# switch.net
KiCad netlist of a schematic drawn in EAGLE
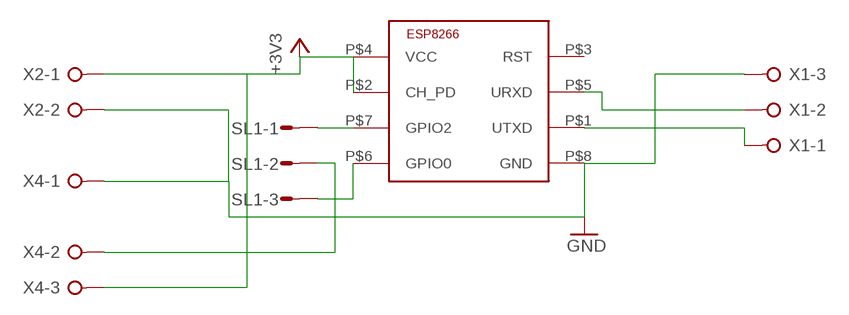
[diagram p0: schematic, sheet 1]

(export (version "E")
  (design (tool "Eeschema 10.0.6"))
  (components
    (comp (ref "SL1")
      (value "M03S")
      (footprint "eagle-import:03P")
      (libsource (lib "eagle-import") (part "M03S"))
    )
    (comp (ref "U$1")
      (value "ESP8266-01")
      (footprint "eagle-import:ESP-01")
      (libsource (lib "eagle-import") (part "ESP8266-01"))
    )
    (comp (ref "X1")
      (value "W237-3E")
      (footprint "eagle-import:W237-3E")
      (libsource (lib "eagle-import") (part "W237-3E"))
    )
    (comp (ref "X2")
      (value "W237-02P")
      (footprint "eagle-import:W237-132")
      (libsource (lib "eagle-import") (part "W237-02P"))
    )
    (comp (ref "X4")
      (value "W237-3E")
      (footprint "eagle-import:W237-3E")
      (libsource (lib "eagle-import") (part "W237-3E"))
    )
  )
  (nets
    (net (code "1") (name "+3V3") (class "Default")
      (node (ref "U$1") (pin "P$2") (pinfunction "CH_PD_P$2") (pintype "bidirectional"))
      (node (ref "U$1") (pin "P$4") (pinfunction "VCC_P$4") (pintype "bidirectional"))
      (node (ref "X2") (pin "1") (pinfunction "KL_1") (pintype "passive"))
      (node (ref "X4") (pin "3") (pinfunction "KL_3") (pintype "passive"))
    )
    (net (code "2") (name "GND") (class "Default")
      (node (ref "U$1") (pin "P$8") (pinfunction "GND_P$8") (pintype "bidirectional"))
      (node (ref "X1") (pin "3") (pinfunction "KL_3") (pintype "passive"))
      (node (ref "X2") (pin "2") (pinfunction "KL_2") (pintype "passive"))
      (node (ref "X4") (pin "1") (pinfunction "KL_1") (pintype "passive"))
    )
    (net (code "3") (name "Net-(SL1A-S)") (class "Default")
      (node (ref "SL1") (pin "1") (pinfunction "S_1") (pintype "passive"))
      (node (ref "U$1") (pin "P$7") (pinfunction "GPIO2_P$7") (pintype "bidirectional"))
    )
    (net (code "4") (name "Net-(SL1B-S)") (class "Default")
      (node (ref "SL1") (pin "2") (pinfunction "S_2") (pintype "passive"))
      (node (ref "X4") (pin "2") (pinfunction "KL_2") (pintype "passive"))
    )
    (net (code "5") (name "Net-(SL1C-S)") (class "Default")
      (node (ref "SL1") (pin "3") (pinfunction "S_3") (pintype "passive"))
      (node (ref "U$1") (pin "P$6") (pinfunction "GPIO0_P$6") (pintype "bidirectional"))
    )
    (net (code "6") (name "Net-(U$1-URXD)") (class "Default")
      (node (ref "U$1") (pin "P$5") (pinfunction "URXD_P$5") (pintype "bidirectional"))
      (node (ref "X1") (pin "2") (pinfunction "KL_2") (pintype "passive"))
    )
    (net (code "7") (name "Net-(U$1-UTXD)") (class "Default")
      (node (ref "U$1") (pin "P$1") (pinfunction "UTXD_P$1") (pintype "bidirectional"))
      (node (ref "X1") (pin "1") (pinfunction "KL_1") (pintype "passive"))
    )
    (net (code "8") (name "unconnected-(U$1-RST-PadP$3)") (class "Default")
      (node (ref "U$1") (pin "P$3") (pinfunction "RST_P$3") (pintype "bidirectional"))
    )
  )
)
